# Adafruit_Slider_Trinkey.net
KiCad netlist of a schematic drawn in EAGLE
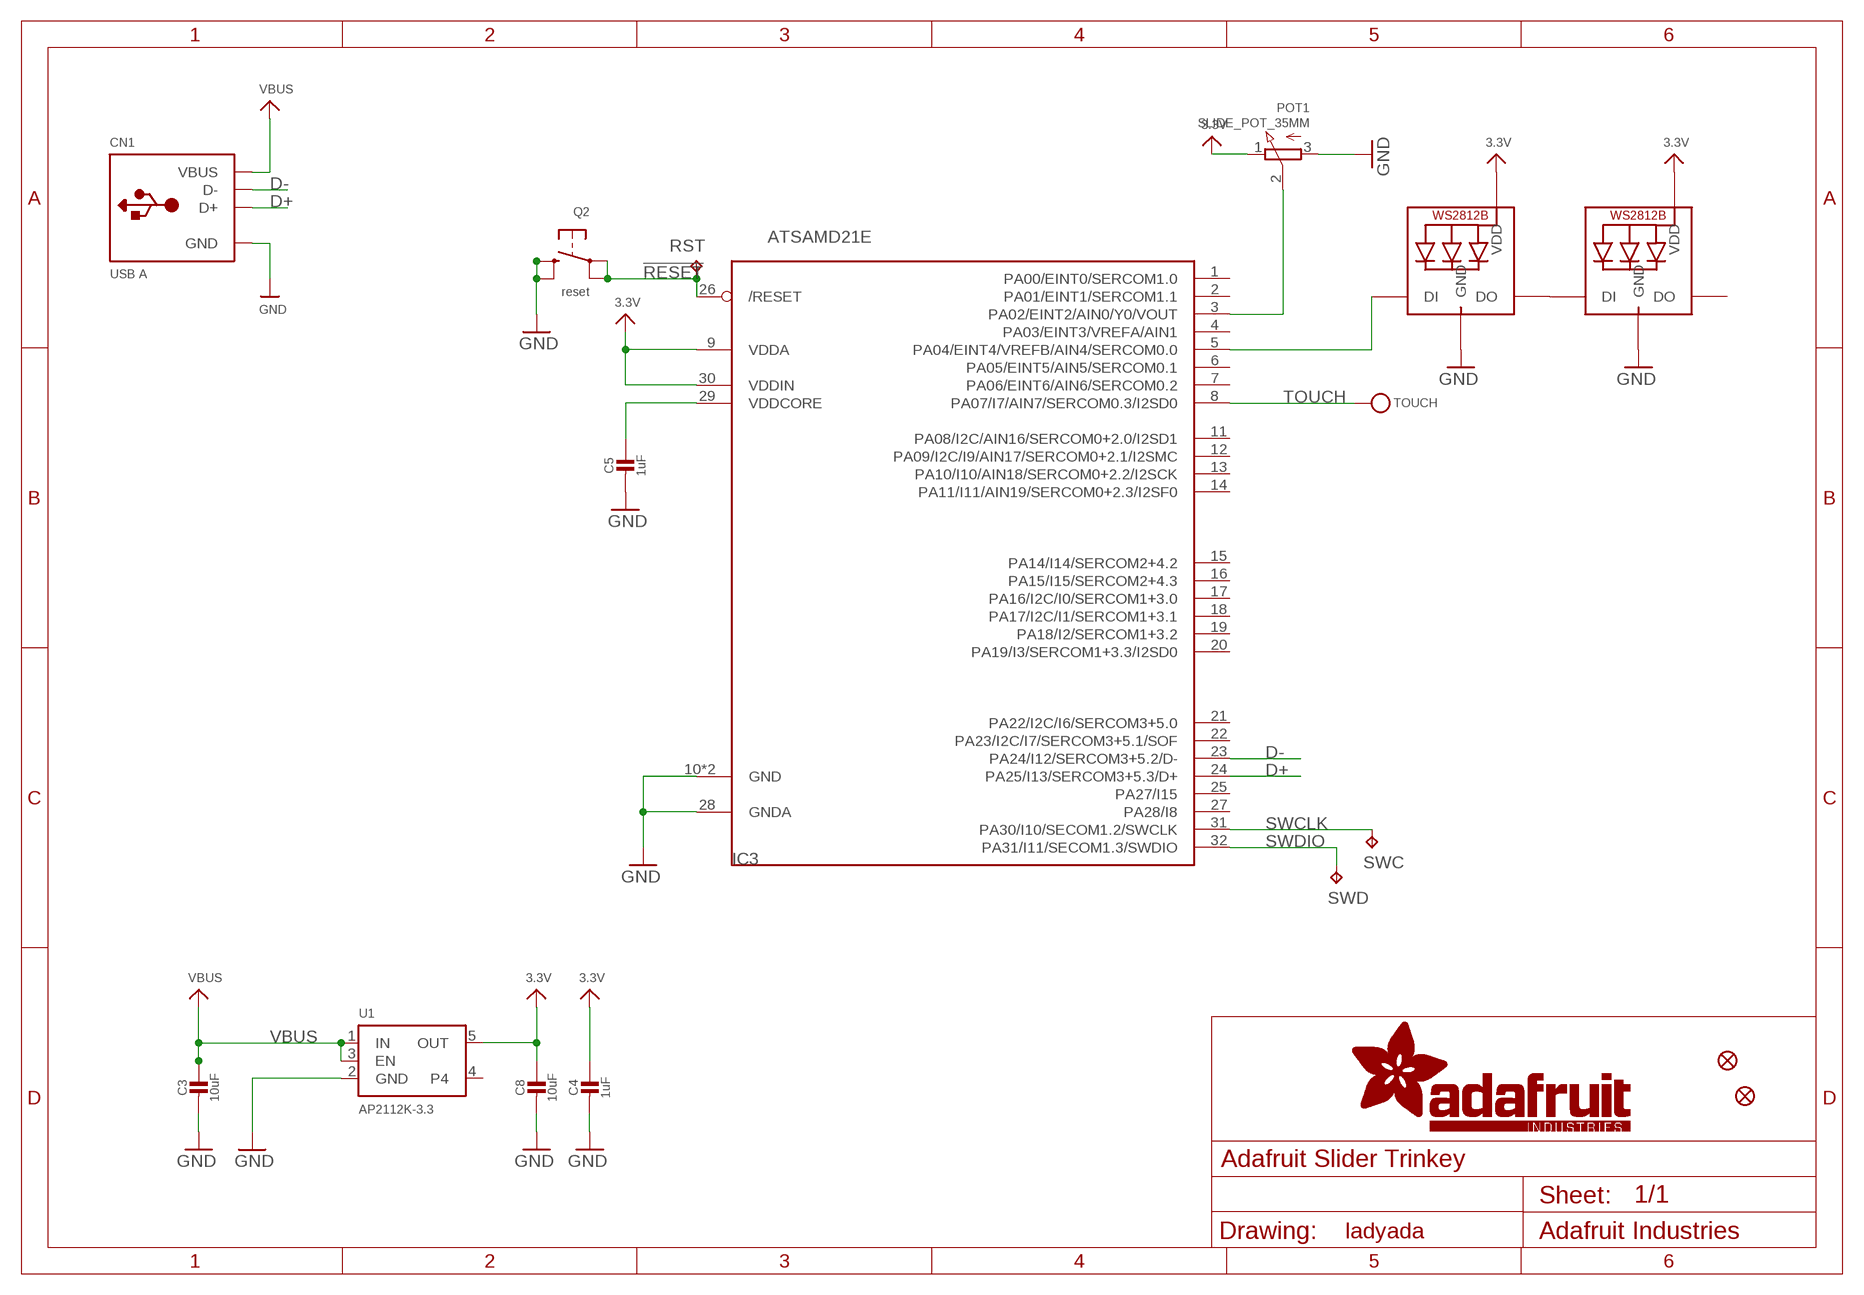
[diagram p0: schematic, sheet 1]

(export (version "E")
  (design (tool "Eeschema 10.0.6"))
  (components
    (comp (ref "C3")
      (value "10uF")
      (footprint "eagle-import:0805-NO")
      (libsource (lib "eagle-import") (part "CAP_CERAMIC0805-NOOUTLINE"))
    )
    (comp (ref "C4")
      (value "1uF")
      (footprint "eagle-import:0603-NO")
      (libsource (lib "eagle-import") (part "CAP_CERAMIC0603_NO"))
    )
    (comp (ref "C5")
      (value "1uF")
      (footprint "eagle-import:0603-NO")
      (libsource (lib "eagle-import") (part "CAP_CERAMIC0603_NO"))
    )
    (comp (ref "C8")
      (value "10uF")
      (footprint "eagle-import:0805-NO")
      (libsource (lib "eagle-import") (part "CAP_CERAMIC0805-NOOUTLINE"))
    )
    (comp (ref "CN1")
      (value "USB A")
      (footprint "eagle-import:USBA_PCB")
      (libsource (lib "eagle-import") (part "USB_TYPEAPCB"))
    )
    (comp (ref "FID1")
      (value "FIDUCIAL_1MM")
      (footprint "eagle-import:FIDUCIAL_1MM")
      (libsource (lib "eagle-import") (part "FIDUCIAL_1MM"))
    )
    (comp (ref "FID2")
      (value "FIDUCIAL_1MM")
      (footprint "eagle-import:FIDUCIAL_1MM")
      (libsource (lib "eagle-import") (part "FIDUCIAL_1MM"))
    )
    (comp (ref "IC3")
      (value "ATSAMD21E")
      (footprint "eagle-import:QFN32_5MM")
      (libsource (lib "eagle-import") (part "ATSAMD21E"))
    )
    (comp (ref "LED1")
      (value "WS2812B_SK6812E")
      (footprint "eagle-import:NEO3535_REVERSE")
      (libsource (lib "eagle-import") (part "WS2812B_SK6812E"))
    )
    (comp (ref "LED2")
      (value "WS2812B_SK6812E")
      (footprint "eagle-import:NEO3535_REVERSE")
      (libsource (lib "eagle-import") (part "WS2812B_SK6812E"))
    )
    (comp (ref "POT1")
      (value "SLIDE_POT_35MM")
      (footprint "eagle-import:SLIDE_POT_35MM")
      (libsource (lib "eagle-import") (part "SLIDE_POT_35MM"))
    )
    (comp (ref "Q2")
      (value "reset")
      (footprint "eagle-import:BTN_KMR2_4.6X2.8")
      (libsource (lib "eagle-import") (part "SWITCH_TACT_SMT4.6X2.8"))
    )
    (comp (ref "RST")
      (value "TPTP16R")
      (footprint "eagle-import:TP16R")
      (libsource (lib "eagle-import") (part "TPTP16R"))
    )
    (comp (ref "SWC")
      (value "TPTP15R")
      (footprint "eagle-import:TP15R")
      (libsource (lib "eagle-import") (part "TPTP15R"))
    )
    (comp (ref "SWD")
      (value "TPTP16R")
      (footprint "eagle-import:TP16R")
      (libsource (lib "eagle-import") (part "TPTP16R"))
    )
    (comp (ref "TOUCH")
      (value "TESTPOINTROUND0.5MM")
      (footprint "eagle-import:TESTPOINT_ROUND_0.5MM")
      (libsource (lib "eagle-import") (part "TESTPOINTROUND0.5MM"))
    )
    (comp (ref "U1")
      (value "AP2112K-3.3")
      (footprint "eagle-import:SOT23-5")
      (libsource (lib "eagle-import") (part "VREG_SOT23-5"))
    )
  )
  (nets
    (net (code "1") (name "/D+") (class "Default")
      (node (ref "CN1") (pin "USB_PLUS") (pinfunction "D+_USB_PLUS") (pintype "bidirectional"))
      (node (ref "IC3") (pin "24") (pinfunction "PA25/I13/SERCOM3+5.3/D+_24") (pintype "bidirectional"))
    )
    (net (code "2") (name "/D-") (class "Default")
      (node (ref "CN1") (pin "USB_NEG") (pinfunction "D-_USB_NEG") (pintype "bidirectional"))
      (node (ref "IC3") (pin "23") (pinfunction "PA24/I12/SERCOM3+5.2/D-_23") (pintype "bidirectional"))
    )
    (net (code "3") (name "/SWCLK") (class "Default")
      (node (ref "IC3") (pin "31") (pinfunction "PA30/I10/SECOM1.2/SWCLK_31") (pintype "bidirectional"))
      (node (ref "SWC") (pin "TP") (pinfunction "TP_TP") (pintype "input"))
    )
    (net (code "4") (name "/SWDIO") (class "Default")
      (node (ref "IC3") (pin "32") (pinfunction "PA31/I11/SECOM1.3/SWDIO_32") (pintype "bidirectional"))
      (node (ref "SWD") (pin "TP") (pinfunction "TP_TP") (pintype "input"))
    )
    (net (code "5") (name "/TOUCH") (class "Default")
      (node (ref "IC3") (pin "8") (pinfunction "PA07/I7/AIN7/SERCOM0.3/I2SD0_8") (pintype "bidirectional"))
      (node (ref "TOUCH") (pin "P$1") (pinfunction "P$1_P$1") (pintype "bidirectional"))
    )
    (net (code "6") (name "/~{RESET}") (class "Default")
      (node (ref "IC3") (pin "26") (pinfunction "/RESET_26") (pintype "bidirectional"))
      (node (ref "Q2") (pin "A") (pinfunction "P_A") (pintype "passive"))
      (node (ref "Q2") (pin "A'") (pinfunction "P1_A'") (pintype "passive"))
      (node (ref "RST") (pin "TP") (pinfunction "TP_TP") (pintype "input"))
    )
    (net (code "7") (name "3.3V") (class "Default")
      (node (ref "C4") (pin "1") (pinfunction "1_1") (pintype "passive"))
      (node (ref "C8") (pin "1") (pinfunction "1_1") (pintype "passive"))
      (node (ref "IC3") (pin "30") (pinfunction "VDDIN_30") (pintype "power_in"))
      (node (ref "IC3") (pin "9") (pinfunction "VDDA_9") (pintype "power_in"))
      (node (ref "LED1") (pin "1-VDD") (pinfunction "VDD_1-VDD") (pintype "power_in"))
      (node (ref "LED2") (pin "1-VDD") (pinfunction "VDD_1-VDD") (pintype "power_in"))
      (node (ref "POT1") (pin "1") (pinfunction "E_1") (pintype "passive"))
      (node (ref "U1") (pin "5") (pinfunction "OUT_5") (pintype "power_in"))
    )
    (net (code "8") (name "GND") (class "Default")
      (node (ref "C3") (pin "2") (pinfunction "2_2") (pintype "passive"))
      (node (ref "C4") (pin "2") (pinfunction "2_2") (pintype "passive"))
      (node (ref "C5") (pin "2") (pinfunction "2_2") (pintype "passive"))
      (node (ref "C8") (pin "2") (pinfunction "2_2") (pintype "passive"))
      (node (ref "CN1") (pin "GND") (pinfunction "GND_GND") (pintype "power_in"))
      (node (ref "IC3") (pin "10") (pinfunction "GND_10") (pintype "power_in"))
      (node (ref "IC3") (pin "28") (pinfunction "GNDA_28") (pintype "power_in"))
      (node (ref "IC3") (pin "33") (pinfunction "GND_33") (pintype "power_in"))
      (node (ref "LED1") (pin "3-GND") (pinfunction "GND_3-GND") (pintype "power_in"))
      (node (ref "LED2") (pin "3-GND") (pinfunction "GND_3-GND") (pintype "power_in"))
      (node (ref "POT1") (pin "3") (pinfunction "A_3") (pintype "passive"))
      (node (ref "Q2") (pin "B") (pinfunction "S_B") (pintype "passive"))
      (node (ref "Q2") (pin "B'") (pinfunction "S1_B'") (pintype "passive"))
      (node (ref "U1") (pin "2") (pinfunction "GND_2") (pintype "power_in"))
    )
    (net (code "9") (name "Net-(IC3-PA02{slash}EINT2{slash}AIN0{slash}Y0{slash}VOUT)") (class "Default")
      (node (ref "IC3") (pin "3") (pinfunction "PA02/EINT2/AIN0/Y0/VOUT_3") (pintype "bidirectional"))
      (node (ref "POT1") (pin "2") (pinfunction "S_2") (pintype "passive"))
    )
    (net (code "10") (name "Net-(IC3-PA04{slash}EINT4{slash}VREFB{slash}AIN4{slash}SERCOM0.0)") (class "Default")
      (node (ref "IC3") (pin "5") (pinfunction "PA04/EINT4/VREFB/AIN4/SERCOM0.0_5") (pintype "bidirectional"))
      (node (ref "LED1") (pin "4-DIN") (pinfunction "DI_4-DIN") (pintype "input"))
    )
    (net (code "11") (name "Net-(IC3-VDDCORE)") (class "Default")
      (node (ref "C5") (pin "1") (pinfunction "1_1") (pintype "passive"))
      (node (ref "IC3") (pin "29") (pinfunction "VDDCORE_29") (pintype "power_in"))
    )
    (net (code "12") (name "Net-(LED1-DO)") (class "Default")
      (node (ref "LED1") (pin "2-DOUT") (pinfunction "DO_2-DOUT") (pintype "output"))
      (node (ref "LED2") (pin "4-DIN") (pinfunction "DI_4-DIN") (pintype "input"))
    )
    (net (code "13") (name "VBUS") (class "Default")
      (node (ref "C3") (pin "1") (pinfunction "1_1") (pintype "passive"))
      (node (ref "CN1") (pin "VCC") (pinfunction "VBUS_VCC") (pintype "power_in"))
      (node (ref "U1") (pin "1") (pinfunction "IN_1") (pintype "power_in"))
      (node (ref "U1") (pin "3") (pinfunction "EN_3") (pintype "input"))
    )
    (net (code "14") (name "unconnected-(IC3-PA00{slash}EINT0{slash}SERCOM1.0-Pad1)") (class "Default")
      (node (ref "IC3") (pin "1") (pinfunction "PA00/EINT0/SERCOM1.0_1") (pintype "bidirectional"))
    )
    (net (code "15") (name "unconnected-(IC3-PA01{slash}EINT1{slash}SERCOM1.1-Pad2)") (class "Default")
      (node (ref "IC3") (pin "2") (pinfunction "PA01/EINT1/SERCOM1.1_2") (pintype "bidirectional"))
    )
    (net (code "16") (name "unconnected-(IC3-PA03{slash}EINT3{slash}VREFA{slash}AIN1-Pad4)") (class "Default")
      (node (ref "IC3") (pin "4") (pinfunction "PA03/EINT3/VREFA/AIN1_4") (pintype "bidirectional"))
    )
    (net (code "17") (name "unconnected-(IC3-PA05{slash}EINT5{slash}AIN5{slash}SERCOM0.1-Pad6)") (class "Default")
      (node (ref "IC3") (pin "6") (pinfunction "PA05/EINT5/AIN5/SERCOM0.1_6") (pintype "bidirectional"))
    )
    (net (code "18") (name "unconnected-(IC3-PA06{slash}EINT6{slash}AIN6{slash}SERCOM0.2-Pad7)") (class "Default")
      (node (ref "IC3") (pin "7") (pinfunction "PA06/EINT6/AIN6/SERCOM0.2_7") (pintype "bidirectional"))
    )
    (net (code "19") (name "unconnected-(IC3-PA08{slash}I2C{slash}AIN16{slash}SERCOM0+2.0{slash}I2SD1-Pad11)") (class "Default")
      (node (ref "IC3") (pin "11") (pinfunction "PA08/I2C/AIN16/SERCOM0+2.0/I2SD1_11") (pintype "bidirectional"))
    )
    (net (code "20") (name "unconnected-(IC3-PA09{slash}I2C{slash}I9{slash}AIN17{slash}SERCOM0+2.1{slash}I2SMC-Pad12)") (class "Default")
      (node (ref "IC3") (pin "12") (pinfunction "PA09/I2C/I9/AIN17/SERCOM0+2.1/I2SMC_12") (pintype "bidirectional"))
    )
    (net (code "21") (name "unconnected-(IC3-PA10{slash}I10{slash}AIN18{slash}SERCOM0+2.2{slash}I2SCK-Pad13)") (class "Default")
      (node (ref "IC3") (pin "13") (pinfunction "PA10/I10/AIN18/SERCOM0+2.2/I2SCK_13") (pintype "bidirectional"))
    )
    (net (code "22") (name "unconnected-(IC3-PA11{slash}I11{slash}AIN19{slash}SERCOM0+2.3{slash}I2SF0-Pad14)") (class "Default")
      (node (ref "IC3") (pin "14") (pinfunction "PA11/I11/AIN19/SERCOM0+2.3/I2SF0_14") (pintype "bidirectional"))
    )
    (net (code "23") (name "unconnected-(IC3-PA14{slash}I14{slash}SERCOM2+4.2-Pad15)") (class "Default")
      (node (ref "IC3") (pin "15") (pinfunction "PA14/I14/SERCOM2+4.2_15") (pintype "bidirectional"))
    )
    (net (code "24") (name "unconnected-(IC3-PA15{slash}I15{slash}SERCOM2+4.3-Pad16)") (class "Default")
      (node (ref "IC3") (pin "16") (pinfunction "PA15/I15/SERCOM2+4.3_16") (pintype "bidirectional"))
    )
    (net (code "25") (name "unconnected-(IC3-PA16{slash}I2C{slash}I0{slash}SERCOM1+3.0-Pad17)") (class "Default")
      (node (ref "IC3") (pin "17") (pinfunction "PA16/I2C/I0/SERCOM1+3.0_17") (pintype "bidirectional"))
    )
    (net (code "26") (name "unconnected-(IC3-PA17{slash}I2C{slash}I1{slash}SERCOM1+3.1-Pad18)") (class "Default")
      (node (ref "IC3") (pin "18") (pinfunction "PA17/I2C/I1/SERCOM1+3.1_18") (pintype "bidirectional"))
    )
    (net (code "27") (name "unconnected-(IC3-PA18{slash}I2{slash}SERCOM1+3.2-Pad19)") (class "Default")
      (node (ref "IC3") (pin "19") (pinfunction "PA18/I2/SERCOM1+3.2_19") (pintype "bidirectional"))
    )
    (net (code "28") (name "unconnected-(IC3-PA19{slash}I3{slash}SERCOM1+3.3{slash}I2SD0-Pad20)") (class "Default")
      (node (ref "IC3") (pin "20") (pinfunction "PA19/I3/SERCOM1+3.3/I2SD0_20") (pintype "bidirectional"))
    )
    (net (code "29") (name "unconnected-(IC3-PA22{slash}I2C{slash}I6{slash}SERCOM3+5.0-Pad21)") (class "Default")
      (node (ref "IC3") (pin "21") (pinfunction "PA22/I2C/I6/SERCOM3+5.0_21") (pintype "bidirectional"))
    )
    (net (code "30") (name "unconnected-(IC3-PA23{slash}I2C{slash}I7{slash}SERCOM3+5.1{slash}SOF-Pad22)") (class "Default")
      (node (ref "IC3") (pin "22") (pinfunction "PA23/I2C/I7/SERCOM3+5.1/SOF_22") (pintype "bidirectional"))
    )
    (net (code "31") (name "unconnected-(IC3-PA27{slash}I15-Pad25)") (class "Default")
      (node (ref "IC3") (pin "25") (pinfunction "PA27/I15_25") (pintype "bidirectional"))
    )
    (net (code "32") (name "unconnected-(IC3-PA28{slash}I8-Pad27)") (class "Default")
      (node (ref "IC3") (pin "27") (pinfunction "PA28/I8_27") (pintype "bidirectional"))
    )
    (net (code "33") (name "unconnected-(LED2-DO-Pad2-DOUT)") (class "Default")
      (node (ref "LED2") (pin "2-DOUT") (pinfunction "DO_2-DOUT") (pintype "output"))
    )
    (net (code "34") (name "unconnected-(U1-P4-Pad4)") (class "Default")
      (node (ref "U1") (pin "4") (pinfunction "P4_4") (pintype "bidirectional"))
    )
  )
)
